# RPi_header.net
KiCad netlist of a schematic drawn in Altium Designer
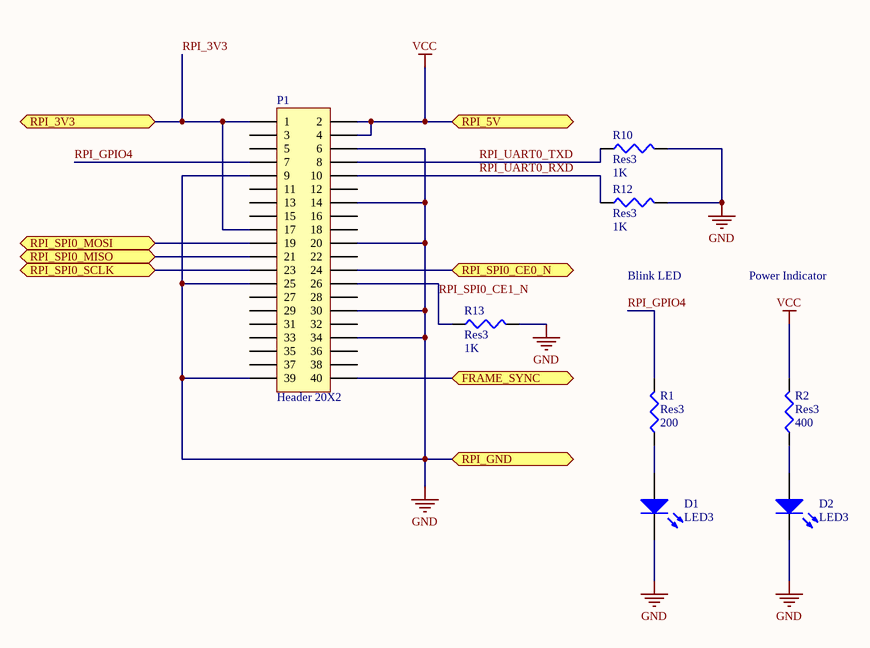
[diagram p0: RPi_header.SchDoc]

(export (version "E")
  (design (tool "Eeschema 10.0.6"))
  (components
    (comp (ref "D1")
      (value "LED3")
      (footprint "3.5X2.8X1.9")
      (description "Typical BLUE SiC LED")
      (fields (field (name "PUBLISHER") "Altium Limited"))
      (libsource (lib "Miscellaneous Devices") (part "LED3"))
    )
    (comp (ref "D2")
      (value "LED3")
      (footprint "3.5X2.8X1.9")
      (description "Typical BLUE SiC LED")
      (fields (field (name "PUBLISHER") "Altium Limited"))
      (libsource (lib "Miscellaneous Devices") (part "LED3"))
    )
    (comp (ref "P1")
      (value "Header 20X2")
      (footprint "HDR2X20")
      (description "Header, 20-Pin, Dual row")
      (fields (field (name "PUBLISHER") "Altium Limited"))
      (libsource (lib "Miscellaneous Connectors") (part "Header 20X2"))
    )
    (comp (ref "R1")
      (value "Res3")
      (footprint "J1-0603")
      (description "Resistor")
      (fields (field (name "ALTIUM_VALUE") "200") (field (name "PUBLISHER") "Altium Limited"))
      (libsource (lib "Miscellaneous Devices") (part "Res3"))
    )
    (comp (ref "R2")
      (value "Res3")
      (footprint "J1-0603")
      (description "Resistor")
      (fields (field (name "ALTIUM_VALUE") "400") (field (name "PUBLISHER") "Altium Limited"))
      (libsource (lib "Miscellaneous Devices") (part "Res3"))
    )
    (comp (ref "R10")
      (value "Res3")
      (footprint "J1-0603")
      (description "Resistor")
      (fields (field (name "ALTIUM_VALUE") "1K") (field (name "PUBLISHER") "Altium Limited"))
      (libsource (lib "Miscellaneous Devices") (part "Res3"))
    )
    (comp (ref "R12")
      (value "Res3")
      (footprint "J1-0603")
      (description "Resistor")
      (fields (field (name "ALTIUM_VALUE") "1K") (field (name "PUBLISHER") "Altium Limited"))
      (libsource (lib "Miscellaneous Devices") (part "Res3"))
    )
    (comp (ref "R13")
      (value "Res3")
      (footprint "J1-0603")
      (description "Resistor")
      (fields (field (name "ALTIUM_VALUE") "1K") (field (name "PUBLISHER") "Altium Limited"))
      (libsource (lib "Miscellaneous Devices") (part "Res3"))
    )
  )
  (nets
    (net (code "1") (name "/FRAME_SYNC") (class "Default")
      (node (ref "P1") (pin "40") (pinfunction "40_40") (pintype "passive"))
    )
    (net (code "2") (name "/RPI_3V3") (class "Default")
      (node (ref "P1") (pin "1") (pinfunction "1_1") (pintype "passive"))
      (node (ref "P1") (pin "17") (pinfunction "17_17") (pintype "passive"))
    )
    (net (code "3") (name "/RPI_GPIO4") (class "Default")
      (node (ref "P1") (pin "7") (pinfunction "7_7") (pintype "passive"))
      (node (ref "R1") (pin "2") (pinfunction "2_2") (pintype "passive"))
    )
    (net (code "4") (name "/RPI_SPI0_CE0_N") (class "Default")
      (node (ref "P1") (pin "24") (pinfunction "24_24") (pintype "passive"))
    )
    (net (code "5") (name "/RPI_SPI0_CE1_N") (class "Default")
      (node (ref "P1") (pin "26") (pinfunction "26_26") (pintype "passive"))
      (node (ref "R13") (pin "1") (pinfunction "1_1") (pintype "passive"))
    )
    (net (code "6") (name "/RPI_SPI0_MISO") (class "Default")
      (node (ref "P1") (pin "21") (pinfunction "21_21") (pintype "passive"))
    )
    (net (code "7") (name "/RPI_SPI0_MOSI") (class "Default")
      (node (ref "P1") (pin "19") (pinfunction "19_19") (pintype "passive"))
    )
    (net (code "8") (name "/RPI_SPI0_SCLK") (class "Default")
      (node (ref "P1") (pin "23") (pinfunction "23_23") (pintype "passive"))
    )
    (net (code "9") (name "/RPI_UART0_RXD") (class "Default")
      (node (ref "P1") (pin "10") (pinfunction "10_10") (pintype "passive"))
      (node (ref "R12") (pin "1") (pinfunction "1_1") (pintype "passive"))
    )
    (net (code "10") (name "/RPI_UART0_TXD") (class "Default")
      (node (ref "P1") (pin "8") (pinfunction "8_8") (pintype "passive"))
      (node (ref "R10") (pin "1") (pinfunction "1_1") (pintype "passive"))
    )
    (net (code "11") (name "GND") (class "Default")
      (node (ref "D1") (pin "2") (pinfunction "K_2") (pintype "passive"))
      (node (ref "D2") (pin "2") (pinfunction "K_2") (pintype "passive"))
      (node (ref "P1") (pin "14") (pinfunction "14_14") (pintype "passive"))
      (node (ref "P1") (pin "20") (pinfunction "20_20") (pintype "passive"))
      (node (ref "P1") (pin "25") (pinfunction "25_25") (pintype "passive"))
      (node (ref "P1") (pin "30") (pinfunction "30_30") (pintype "passive"))
      (node (ref "P1") (pin "34") (pinfunction "34_34") (pintype "passive"))
      (node (ref "P1") (pin "39") (pinfunction "39_39") (pintype "passive"))
      (node (ref "P1") (pin "6") (pinfunction "6_6") (pintype "passive"))
      (node (ref "P1") (pin "9") (pinfunction "9_9") (pintype "passive"))
      (node (ref "R10") (pin "2") (pinfunction "2_2") (pintype "passive"))
      (node (ref "R12") (pin "2") (pinfunction "2_2") (pintype "passive"))
      (node (ref "R13") (pin "2") (pinfunction "2_2") (pintype "passive"))
    )
    (net (code "12") (name "Net-(D1-A)") (class "Default")
      (node (ref "D1") (pin "1") (pinfunction "A_1") (pintype "passive"))
      (node (ref "R1") (pin "1") (pinfunction "1_1") (pintype "passive"))
    )
    (net (code "13") (name "Net-(D2-A)") (class "Default")
      (node (ref "D2") (pin "1") (pinfunction "A_1") (pintype "passive"))
      (node (ref "R2") (pin "1") (pinfunction "1_1") (pintype "passive"))
    )
    (net (code "14") (name "VCC") (class "Default")
      (node (ref "P1") (pin "2") (pinfunction "2_2") (pintype "passive"))
      (node (ref "P1") (pin "4") (pinfunction "4_4") (pintype "passive"))
      (node (ref "R2") (pin "2") (pinfunction "2_2") (pintype "passive"))
    )
    (net (code "15") (name "unconnected-(P1-Pad3)") (class "Default")
      (node (ref "P1") (pin "3") (pinfunction "3_3") (pintype "passive"))
    )
    (net (code "16") (name "unconnected-(P1-Pad5)") (class "Default")
      (node (ref "P1") (pin "5") (pinfunction "5_5") (pintype "passive"))
    )
    (net (code "17") (name "unconnected-(P1-Pad11)") (class "Default")
      (node (ref "P1") (pin "11") (pinfunction "11_11") (pintype "passive"))
    )
    (net (code "18") (name "unconnected-(P1-Pad12)") (class "Default")
      (node (ref "P1") (pin "12") (pinfunction "12_12") (pintype "passive"))
    )
    (net (code "19") (name "unconnected-(P1-Pad13)") (class "Default")
      (node (ref "P1") (pin "13") (pinfunction "13_13") (pintype "passive"))
    )
    (net (code "20") (name "unconnected-(P1-Pad15)") (class "Default")
      (node (ref "P1") (pin "15") (pinfunction "15_15") (pintype "passive"))
    )
    (net (code "21") (name "unconnected-(P1-Pad16)") (class "Default")
      (node (ref "P1") (pin "16") (pinfunction "16_16") (pintype "passive"))
    )
    (net (code "22") (name "unconnected-(P1-Pad18)") (class "Default")
      (node (ref "P1") (pin "18") (pinfunction "18_18") (pintype "passive"))
    )
    (net (code "23") (name "unconnected-(P1-Pad22)") (class "Default")
      (node (ref "P1") (pin "22") (pinfunction "22_22") (pintype "passive"))
    )
    (net (code "24") (name "unconnected-(P1-Pad27)") (class "Default")
      (node (ref "P1") (pin "27") (pinfunction "27_27") (pintype "passive"))
    )
    (net (code "25") (name "unconnected-(P1-Pad28)") (class "Default")
      (node (ref "P1") (pin "28") (pinfunction "28_28") (pintype "passive"))
    )
    (net (code "26") (name "unconnected-(P1-Pad29)") (class "Default")
      (node (ref "P1") (pin "29") (pinfunction "29_29") (pintype "passive"))
    )
    (net (code "27") (name "unconnected-(P1-Pad31)") (class "Default")
      (node (ref "P1") (pin "31") (pinfunction "31_31") (pintype "passive"))
    )
    (net (code "28") (name "unconnected-(P1-Pad32)") (class "Default")
      (node (ref "P1") (pin "32") (pinfunction "32_32") (pintype "passive"))
    )
    (net (code "29") (name "unconnected-(P1-Pad33)") (class "Default")
      (node (ref "P1") (pin "33") (pinfunction "33_33") (pintype "passive"))
    )
    (net (code "30") (name "unconnected-(P1-Pad35)") (class "Default")
      (node (ref "P1") (pin "35") (pinfunction "35_35") (pintype "passive"))
    )
    (net (code "31") (name "unconnected-(P1-Pad36)") (class "Default")
      (node (ref "P1") (pin "36") (pinfunction "36_36") (pintype "passive"))
    )
    (net (code "32") (name "unconnected-(P1-Pad37)") (class "Default")
      (node (ref "P1") (pin "37") (pinfunction "37_37") (pintype "passive"))
    )
    (net (code "33") (name "unconnected-(P1-Pad38)") (class "Default")
      (node (ref "P1") (pin "38") (pinfunction "38_38") (pintype "passive"))
    )
  )
)
